# IR_Detector.net
KiCad netlist of a schematic drawn in EAGLE
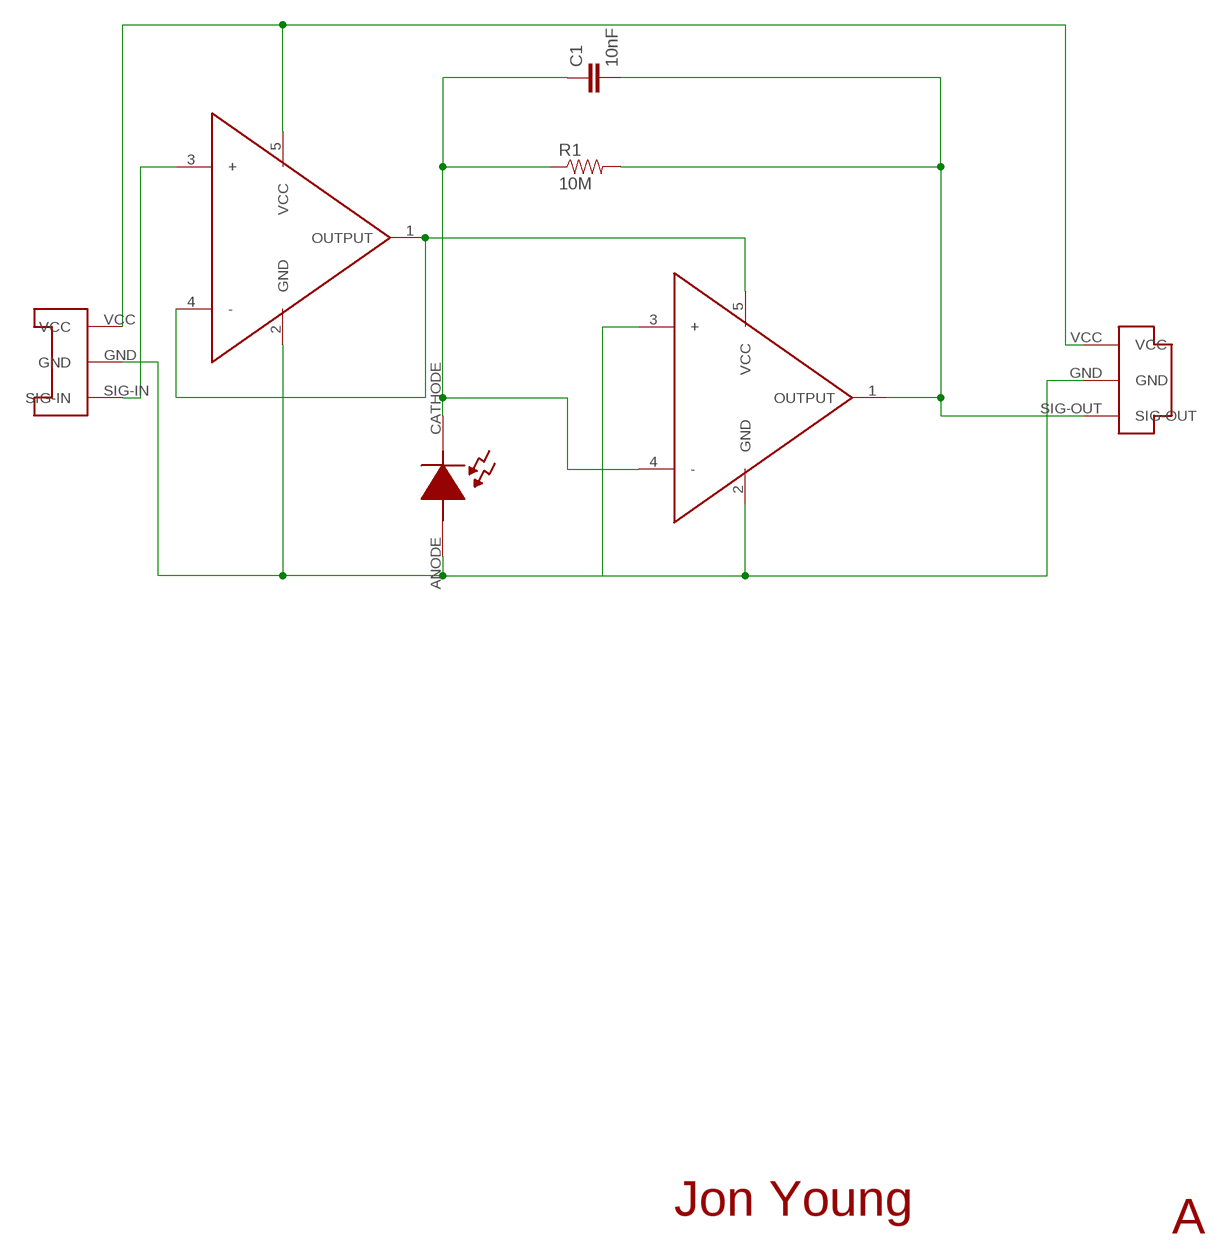
[diagram p0: schematic, sheet 1]

(export (version "E")
  (design (tool "Eeschema 10.0.6"))
  (components
    (comp (ref "C1")
      (value "10nF")
      (footprint "eagle-import:0603-CAP")
      (libsource (lib "eagle-import") (part "CAP0603-CAP"))
    )
    (comp (ref "R1")
      (value "10M")
      (footprint "eagle-import:0603-RES")
      (libsource (lib "eagle-import") (part "RESISTOR0603"))
    )
    (comp (ref "U$1")
      (value "CONN-PLUG-3POS-3MM")
      (footprint "eagle-import:PLUG-3POS-3MM-SMD")
      (libsource (lib "eagle-import") (part "CONN-PLUG-3POS-3MM"))
    )
    (comp (ref "U$2")
      (value "CONN-SOCKET-3POS-3MM")
      (footprint "eagle-import:SOCKET-3POS-3MM-SMD")
      (libsource (lib "eagle-import") (part "CONN-SOCKET-3POS-3MM"))
    )
    (comp (ref "U$3")
      (value "VEMD2020")
      (footprint "eagle-import:VEMD2020X01")
      (libsource (lib "eagle-import") (part "VEMD2020"))
    )
    (comp (ref "U$4")
      (value "OPAMP-MCP6001SC70-5")
      (footprint "eagle-import:SC70")
      (libsource (lib "eagle-import") (part "OPAMP-MCP6001SC70-5"))
    )
    (comp (ref "U$5")
      (value "OPAMP-MCP6001SC70-5")
      (footprint "eagle-import:SC70")
      (libsource (lib "eagle-import") (part "OPAMP-MCP6001SC70-5"))
    )
  )
  (nets
    (net (code "1") (name "Net-(U$4-+)") (class "Default")
      (node (ref "U$1") (pin "GND") (pinfunction "GND_GND") (pintype "power_in"))
      (node (ref "U$2") (pin "GND") (pinfunction "GND_GND") (pintype "power_in"))
      (node (ref "U$3") (pin "ANODE") (pinfunction "ANODE_ANODE") (pintype "passive"))
      (node (ref "U$4") (pin "2") (pinfunction "GND_2") (pintype "power_in"))
      (node (ref "U$4") (pin "3") (pinfunction "+_3") (pintype "input"))
      (node (ref "U$5") (pin "2") (pinfunction "GND_2") (pintype "power_in"))
    )
    (net (code "2") (name "Net-(U$4--)") (class "Default")
      (node (ref "C1") (pin "1") (pinfunction "1_1") (pintype "passive"))
      (node (ref "R1") (pin "1") (pinfunction "1_1") (pintype "passive"))
      (node (ref "U$3") (pin "CATHODE") (pinfunction "CATHODE_CATHODE") (pintype "bidirectional"))
      (node (ref "U$4") (pin "4") (pinfunction "-_4") (pintype "input"))
    )
    (net (code "3") (name "Net-(U$4-OUTPUT)") (class "Default")
      (node (ref "C1") (pin "2") (pinfunction "2_2") (pintype "passive"))
      (node (ref "R1") (pin "2") (pinfunction "2_2") (pintype "passive"))
      (node (ref "U$1") (pin "SIG-OUT") (pinfunction "SIG-OUT_SIG-OUT") (pintype "bidirectional"))
      (node (ref "U$4") (pin "1") (pinfunction "OUTPUT_1") (pintype "output"))
    )
    (net (code "4") (name "Net-(U$4-VCC)") (class "Default")
      (node (ref "U$4") (pin "5") (pinfunction "VCC_5") (pintype "power_in"))
      (node (ref "U$5") (pin "1") (pinfunction "OUTPUT_1") (pintype "output"))
      (node (ref "U$5") (pin "4") (pinfunction "-_4") (pintype "input"))
    )
    (net (code "5") (name "Net-(U$5-+)") (class "Default")
      (node (ref "U$2") (pin "SIG-IN") (pinfunction "SIG-IN_SIG-IN") (pintype "bidirectional"))
      (node (ref "U$5") (pin "3") (pinfunction "+_3") (pintype "input"))
    )
    (net (code "6") (name "Net-(U$5-VCC)") (class "Default")
      (node (ref "U$1") (pin "VCC") (pinfunction "VCC_VCC") (pintype "power_in"))
      (node (ref "U$2") (pin "VCC") (pinfunction "VCC_VCC") (pintype "power_in"))
      (node (ref "U$5") (pin "5") (pinfunction "VCC_5") (pintype "power_in"))
    )
  )
)
